# SchematicAltiumdesigner.net
KiCad netlist of a schematic drawn in Altium Designer
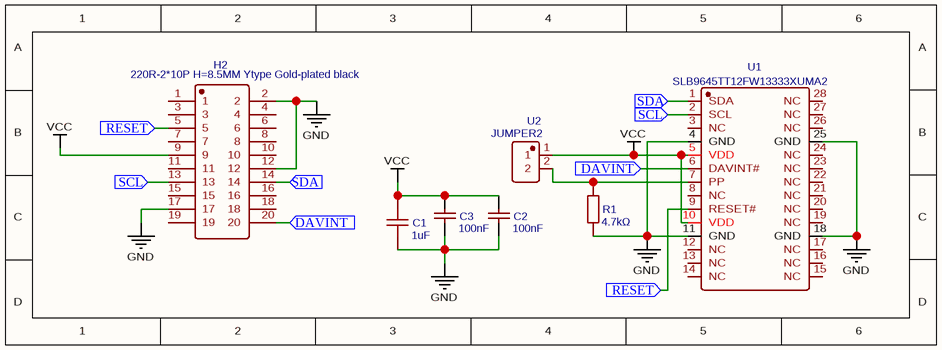
[diagram p0: SchematicAltiumdesigner.schdoc]

(export (version "E")
  (design (tool "Eeschema 10.0.6"))
  (components
    (comp (ref "C1")
      (value "1uF")
      (fields
        (field (name "BOM_MANUFACTURER PART") "CL31B105KBHNNNE")
        (field (name "BOM_SUPPLIER PART") "C1848")
      )
      (libsource (lib "altium-import") (part "root_1_1uF_"))
    )
    (comp (ref "C2")
      (value "100nF")
      (fields
        (field (name "BOM_MANUFACTURER PART") "CL31B104KBCNNNC")
        (field (name "BOM_SUPPLIER PART") "C24497")
      )
      (libsource (lib "altium-import") (part "root_1_100nF_"))
    )
    (comp (ref "C3")
      (value "100nF")
      (fields
        (field (name "BOM_MANUFACTURER PART") "CL31B104KBCNNNC")
        (field (name "BOM_SUPPLIER PART") "C24497")
      )
      (libsource (lib "altium-import") (part "root_1_100nF_"))
    )
    (comp (ref "H2")
      (value "220R-2*10P H=8.5MM Ytype Gold-plated black")
      (fields (field (name "BOM_SUPPLIER PART") "C124406") (field (name "CONTRIBUTOR") "LCSC"))
      (libsource (lib "altium-import") (part "root_0_220R-2*10P H=8.5MM Ytype Gold-plated black_"))
    )
    (comp (ref "R1")
      (value "4.7kΩ")
      (fields
        (field (name "BOM_SUPPLIER PART") "C269760")
        (field (name "BOM_MANUFACTURER PART") "RMC12064.7K5%N")
        (field (name "CONTRIBUTOR") "LCSC")
      )
      (libsource (lib "altium-import") (part "root_3_4.7kΩ_"))
    )
    (comp (ref "U1")
      (value "SLB9645TT12FW13333XUMA2")
      (fields (field (name "BOM_SUPPLIER PART") "C2651707") (field (name "CONTRIBUTOR") "lcsc"))
      (libsource (lib "altium-import") (part "root_0_SLB9645TT12FW13333XUMA2_"))
    )
    (comp (ref "U2")
      (value "JUMPER2")
      (fields
        (field (name "BOM_SUPPLIER PART") "C2940092")
        (field (name "BOM_MANUFACTURER PART") "Jumper2")
        (field (name "CONTRIBUTOR") "LCSC")
      )
      (libsource (lib "altium-import") (part "root_0_JUMPER2_"))
    )
  )
  (nets
    (net (code "1") (name "/DAVINT") (class "Default")
      (node (ref "H2") (pin "20") (pinfunction "20_20") (pintype "passive"))
      (node (ref "U1") (pin "6") (pinfunction "DAVINT#_6") (pintype "passive"))
    )
    (net (code "2") (name "/RESET") (class "Default")
      (node (ref "H2") (pin "5") (pinfunction "5_5") (pintype "passive"))
      (node (ref "U1") (pin "9") (pinfunction "RESET#_9") (pintype "passive"))
    )
    (net (code "3") (name "/SCL") (class "Default")
      (node (ref "H2") (pin "13") (pinfunction "13_13") (pintype "passive"))
      (node (ref "U1") (pin "2") (pinfunction "SCL_2") (pintype "passive"))
    )
    (net (code "4") (name "/SDA") (class "Default")
      (node (ref "H2") (pin "14") (pinfunction "14_14") (pintype "passive"))
      (node (ref "U1") (pin "1") (pinfunction "SDA_1") (pintype "passive"))
    )
    (net (code "5") (name "GND") (class "Default")
      (node (ref "C1") (pin "1") (pinfunction "1_1") (pintype "passive"))
      (node (ref "C2") (pin "1") (pinfunction "1_1") (pintype "passive"))
      (node (ref "C3") (pin "1") (pinfunction "1_1") (pintype "passive"))
      (node (ref "H2") (pin "12") (pinfunction "12_12") (pintype "passive"))
      (node (ref "H2") (pin "17") (pinfunction "17_17") (pintype "passive"))
      (node (ref "H2") (pin "2") (pinfunction "2_2") (pintype "passive"))
      (node (ref "R1") (pin "2") (pinfunction "2_2") (pintype "passive"))
      (node (ref "U1") (pin "11") (pinfunction "GND_11") (pintype "passive"))
      (node (ref "U1") (pin "18") (pinfunction "GND_18") (pintype "passive"))
      (node (ref "U1") (pin "25") (pinfunction "GND_25") (pintype "passive"))
      (node (ref "U1") (pin "4") (pinfunction "GND_4") (pintype "passive"))
    )
    (net (code "6") (name "Net-(U1-PP)") (class "Default")
      (node (ref "R1") (pin "1") (pinfunction "1_1") (pintype "passive"))
      (node (ref "U1") (pin "7") (pinfunction "PP_7") (pintype "passive"))
      (node (ref "U2") (pin "2") (pinfunction "2_2") (pintype "passive"))
    )
    (net (code "7") (name "VCC") (class "Default")
      (node (ref "C1") (pin "2") (pinfunction "2_2") (pintype "passive"))
      (node (ref "C2") (pin "2") (pinfunction "2_2") (pintype "passive"))
      (node (ref "C3") (pin "2") (pinfunction "2_2") (pintype "passive"))
      (node (ref "H2") (pin "9") (pinfunction "9_9") (pintype "passive"))
      (node (ref "U1") (pin "10") (pinfunction "VDD_10") (pintype "passive"))
      (node (ref "U1") (pin "5") (pinfunction "VDD_5") (pintype "passive"))
      (node (ref "U2") (pin "1") (pinfunction "1_1") (pintype "passive"))
    )
    (net (code "8") (name "unconnected-(H2-Pad1)") (class "Default")
      (node (ref "H2") (pin "1") (pinfunction "1_1") (pintype "passive"))
    )
    (net (code "9") (name "unconnected-(H2-Pad3)") (class "Default")
      (node (ref "H2") (pin "3") (pinfunction "3_3") (pintype "passive"))
    )
    (net (code "10") (name "unconnected-(H2-Pad4)") (class "Default")
      (node (ref "H2") (pin "4") (pinfunction "4_4") (pintype "passive"))
    )
    (net (code "11") (name "unconnected-(H2-Pad6)") (class "Default")
      (node (ref "H2") (pin "6") (pinfunction "6_6") (pintype "passive"))
    )
    (net (code "12") (name "unconnected-(H2-Pad7)") (class "Default")
      (node (ref "H2") (pin "7") (pinfunction "7_7") (pintype "passive"))
    )
    (net (code "13") (name "unconnected-(H2-Pad8)") (class "Default")
      (node (ref "H2") (pin "8") (pinfunction "8_8") (pintype "passive"))
    )
    (net (code "14") (name "unconnected-(H2-Pad10)") (class "Default")
      (node (ref "H2") (pin "10") (pinfunction "10_10") (pintype "passive"))
    )
    (net (code "15") (name "unconnected-(H2-Pad11)") (class "Default")
      (node (ref "H2") (pin "11") (pinfunction "11_11") (pintype "passive"))
    )
    (net (code "16") (name "unconnected-(H2-Pad15)") (class "Default")
      (node (ref "H2") (pin "15") (pinfunction "15_15") (pintype "passive"))
    )
    (net (code "17") (name "unconnected-(H2-Pad16)") (class "Default")
      (node (ref "H2") (pin "16") (pinfunction "16_16") (pintype "passive"))
    )
    (net (code "18") (name "unconnected-(H2-Pad18)") (class "Default")
      (node (ref "H2") (pin "18") (pinfunction "18_18") (pintype "passive"))
    )
    (net (code "19") (name "unconnected-(H2-Pad19)") (class "Default")
      (node (ref "H2") (pin "19") (pinfunction "19_19") (pintype "passive"))
    )
    (net (code "20") (name "unconnected-(U1-NC-Pad3)") (class "Default")
      (node (ref "U1") (pin "3") (pinfunction "NC_3") (pintype "passive"))
    )
    (net (code "21") (name "unconnected-(U1-NC-Pad8)") (class "Default")
      (node (ref "U1") (pin "8") (pinfunction "NC_8") (pintype "passive"))
    )
    (net (code "22") (name "unconnected-(U1-NC-Pad12)") (class "Default")
      (node (ref "U1") (pin "12") (pinfunction "NC_12") (pintype "passive"))
    )
    (net (code "23") (name "unconnected-(U1-NC-Pad13)") (class "Default")
      (node (ref "U1") (pin "13") (pinfunction "NC_13") (pintype "passive"))
    )
    (net (code "24") (name "unconnected-(U1-NC-Pad14)") (class "Default")
      (node (ref "U1") (pin "14") (pinfunction "NC_14") (pintype "passive"))
    )
    (net (code "25") (name "unconnected-(U1-NC-Pad15)") (class "Default")
      (node (ref "U1") (pin "15") (pinfunction "NC_15") (pintype "passive"))
    )
    (net (code "26") (name "unconnected-(U1-NC-Pad16)") (class "Default")
      (node (ref "U1") (pin "16") (pinfunction "NC_16") (pintype "passive"))
    )
    (net (code "27") (name "unconnected-(U1-NC-Pad17)") (class "Default")
      (node (ref "U1") (pin "17") (pinfunction "NC_17") (pintype "passive"))
    )
    (net (code "28") (name "unconnected-(U1-NC-Pad19)") (class "Default")
      (node (ref "U1") (pin "19") (pinfunction "NC_19") (pintype "passive"))
    )
    (net (code "29") (name "unconnected-(U1-NC-Pad20)") (class "Default")
      (node (ref "U1") (pin "20") (pinfunction "NC_20") (pintype "passive"))
    )
    (net (code "30") (name "unconnected-(U1-NC-Pad21)") (class "Default")
      (node (ref "U1") (pin "21") (pinfunction "NC_21") (pintype "passive"))
    )
    (net (code "31") (name "unconnected-(U1-NC-Pad22)") (class "Default")
      (node (ref "U1") (pin "22") (pinfunction "NC_22") (pintype "passive"))
    )
    (net (code "32") (name "unconnected-(U1-NC-Pad23)") (class "Default")
      (node (ref "U1") (pin "23") (pinfunction "NC_23") (pintype "passive"))
    )
    (net (code "33") (name "unconnected-(U1-NC-Pad24)") (class "Default")
      (node (ref "U1") (pin "24") (pinfunction "NC_24") (pintype "passive"))
    )
    (net (code "34") (name "unconnected-(U1-NC-Pad26)") (class "Default")
      (node (ref "U1") (pin "26") (pinfunction "NC_26") (pintype "passive"))
    )
    (net (code "35") (name "unconnected-(U1-NC-Pad27)") (class "Default")
      (node (ref "U1") (pin "27") (pinfunction "NC_27") (pintype "passive"))
    )
    (net (code "36") (name "unconnected-(U1-NC-Pad28)") (class "Default")
      (node (ref "U1") (pin "28") (pinfunction "NC_28") (pintype "passive"))
    )
  )
)
